# Main_Board_Module.net
KiCad netlist of a schematic drawn in EAGLE
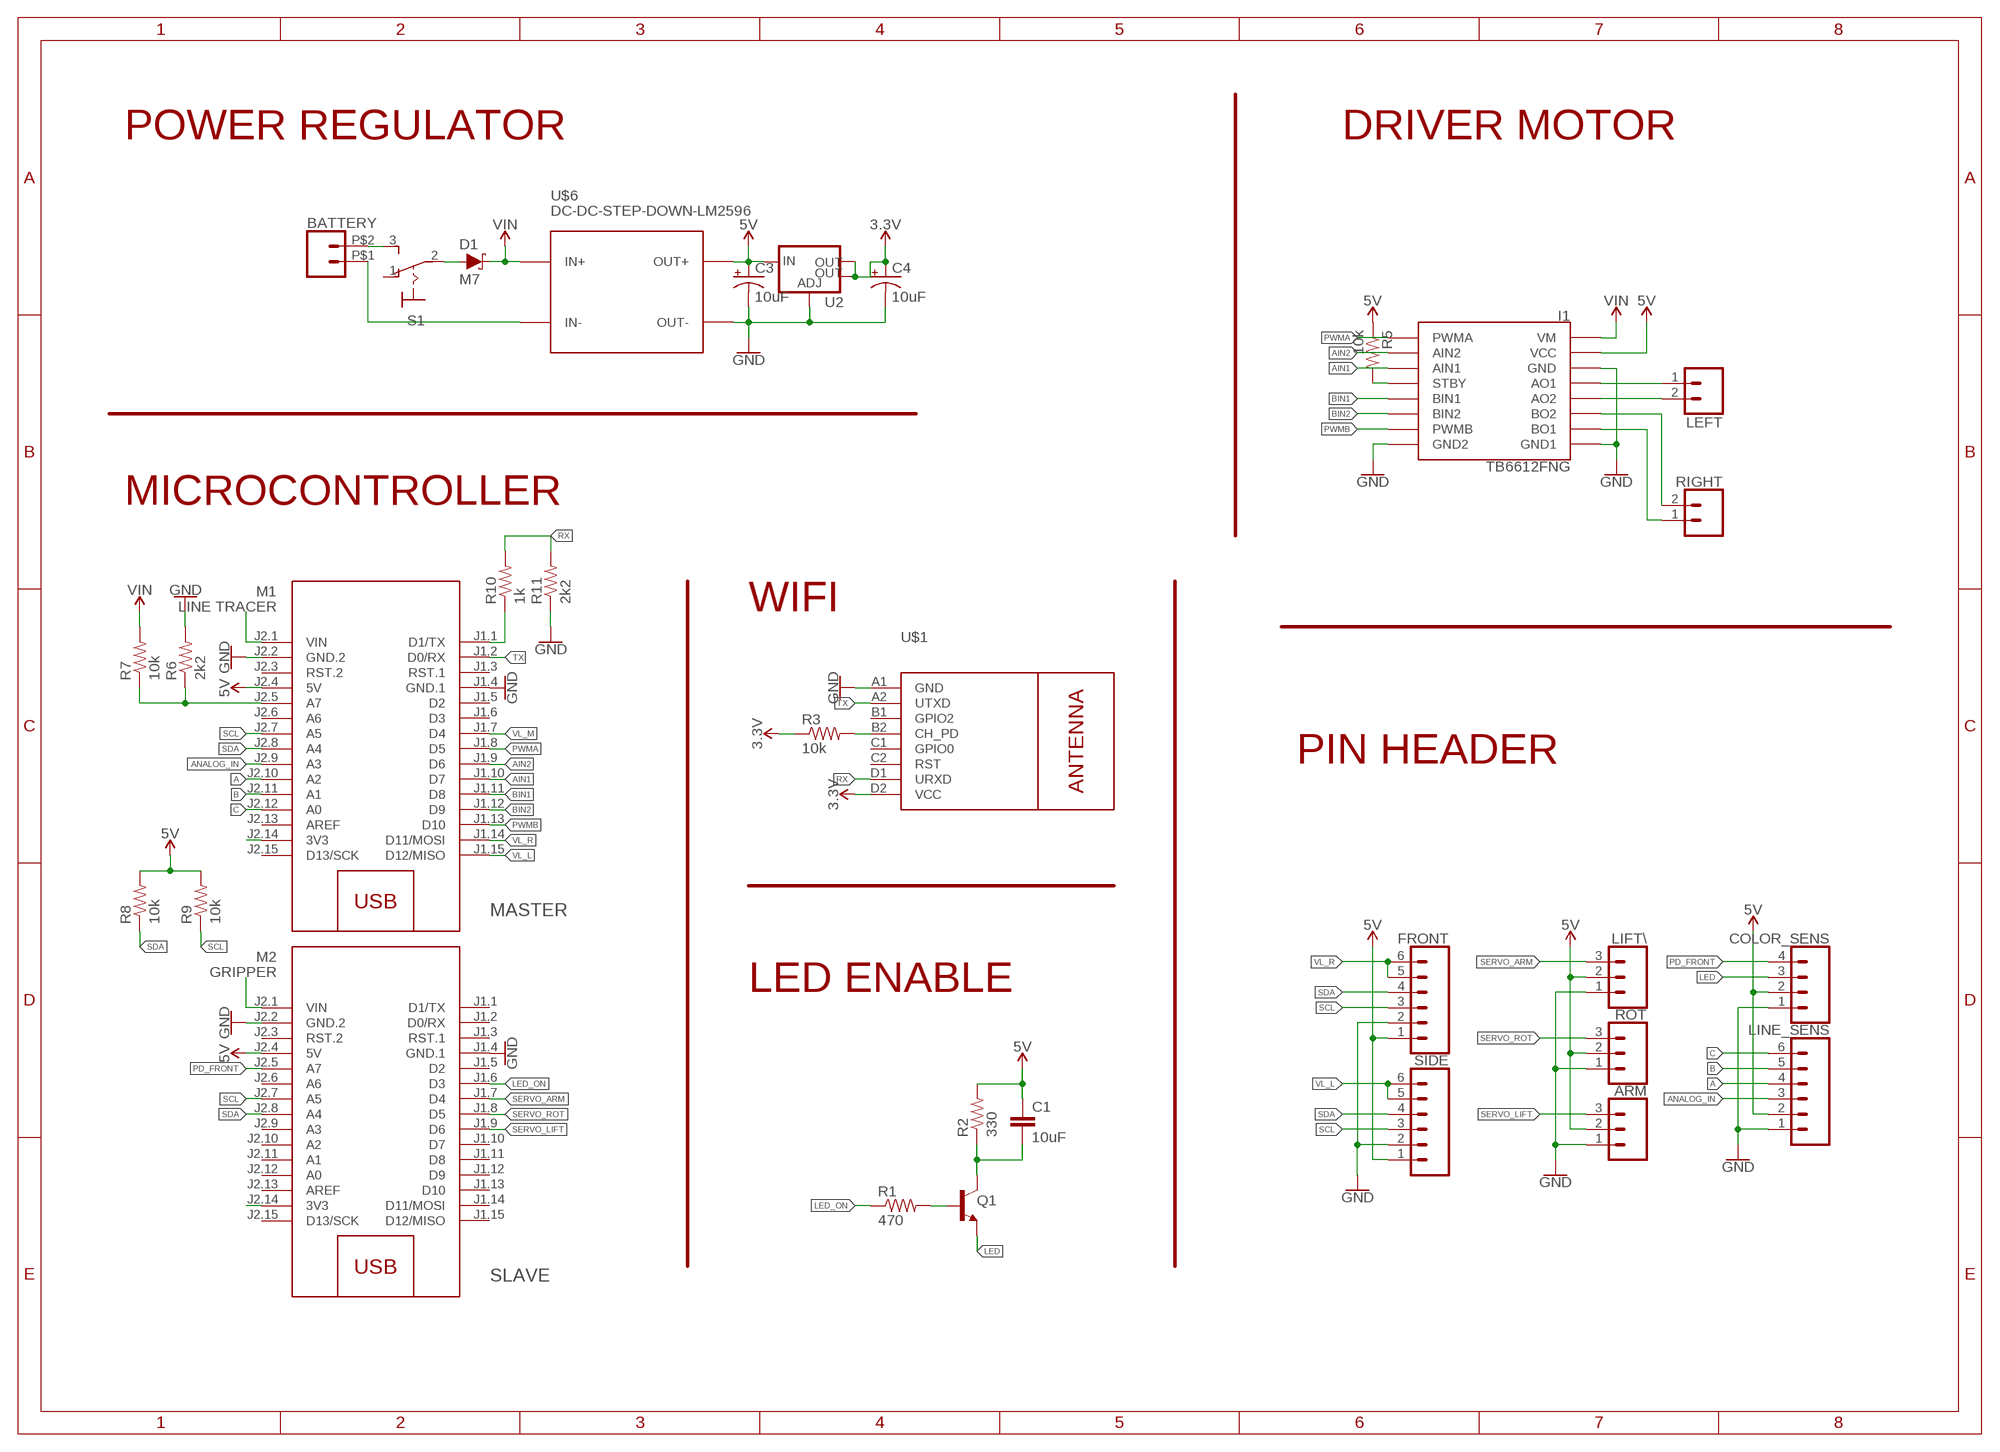
[diagram p0: schematic, sheet 1]

(export (version "E")
  (design (tool "Eeschema 10.0.6"))
  (components
    (comp (ref "ARM")
      (value "CONN_03")
      (footprint "eagle-import:1X03")
      (libsource (lib "eagle-import") (part "CONN_03"))
    )
    (comp (ref "BATTERY")
      (value "CONN_02PTH2")
      (footprint "eagle-import:1X02_BIG")
      (libsource (lib "eagle-import") (part "CONN_02PTH2"))
    )
    (comp (ref "C1")
      (value "10uF")
      (footprint "eagle-import:C1206")
      (libsource (lib "eagle-import") (part "C-EUC1206"))
    )
    (comp (ref "C3")
      (value "10uF")
      (footprint "eagle-import:EIA3216")
      (libsource (lib "eagle-import") (part "10UF-POLAR-EIA3216-16V-10%(TANT)"))
    )
    (comp (ref "C4")
      (value "10uF")
      (footprint "eagle-import:EIA3216")
      (libsource (lib "eagle-import") (part "10UF-POLAR-EIA3216-16V-10%(TANT)"))
    )
    (comp (ref "COLOR_SENS")
      (value "CONN_04")
      (footprint "eagle-import:1X04")
      (libsource (lib "eagle-import") (part "CONN_04"))
    )
    (comp (ref "D1")
      (value "M7")
      (footprint "eagle-import:SMA-DIODE")
      (libsource (lib "eagle-import") (part "DIODE-SCHOTTKY-SS14"))
    )
    (comp (ref "FRONT")
      (value "CONN_06SILK_FEMALE_PTH")
      (footprint "eagle-import:1X06")
      (libsource (lib "eagle-import") (part "CONN_06SILK_FEMALE_PTH"))
    )
    (comp (ref "I1")
      (value "TB6612FNG_MODULE")
      (footprint "eagle-import:TB6612FNG")
      (libsource (lib "eagle-import") (part "TB6612FNG_MODULE"))
    )
    (comp (ref "LEFT")
      (value "CONN_02POLAR")
      (footprint "eagle-import:MOLEX-1X2")
      (libsource (lib "eagle-import") (part "CONN_02POLAR"))
    )
    (comp (ref "LIFT\\")
      (value "CONN_03")
      (footprint "eagle-import:1X03")
      (libsource (lib "eagle-import") (part "CONN_03"))
    )
    (comp (ref "LINE_SENS")
      (value "CONN_06SILK_FEMALE_PTH")
      (footprint "eagle-import:1X06")
      (libsource (lib "eagle-import") (part "CONN_06SILK_FEMALE_PTH"))
    )
    (comp (ref "M1")
      (value "LINE TRACER")
      (footprint "eagle-import:ARDUINO-NANO-3.0")
      (libsource (lib "eagle-import") (part "ARDUINO-NANO-3.0"))
    )
    (comp (ref "M2")
      (value "GRIPPER")
      (footprint "eagle-import:ARDUINO-NANO-3.0")
      (libsource (lib "eagle-import") (part "ARDUINO-NANO-3.0"))
    )
    (comp (ref "Q1")
      (value "TRANS_NPN-MMBT2222AL")
      (footprint "eagle-import:SOT23-3")
      (libsource (lib "eagle-import") (part "TRANS_NPN-MMBT2222AL"))
    )
    (comp (ref "R1")
      (value "470")
      (footprint "eagle-import:R1206")
      (libsource (lib "eagle-import") (part "rcl_334_R-US_R1206"))
    )
    (comp (ref "R2")
      (value "330")
      (footprint "eagle-import:R1206")
      (libsource (lib "eagle-import") (part "rcl_334_R-US_R1206"))
    )
    (comp (ref "R3")
      (value "10k")
      (footprint "eagle-import:R1206")
      (libsource (lib "eagle-import") (part "rcl_334_R-US_R1206"))
    )
    (comp (ref "R5")
      (value "10k")
      (footprint "eagle-import:0207_9")
      (libsource (lib "eagle-import") (part "R-US_0207/9"))
    )
    (comp (ref "R6")
      (value "2k2")
      (footprint "eagle-import:0207_9")
      (libsource (lib "eagle-import") (part "R-US_0207/9"))
    )
    (comp (ref "R7")
      (value "10k")
      (footprint "eagle-import:0207_9")
      (libsource (lib "eagle-import") (part "R-US_0207/9"))
    )
    (comp (ref "R8")
      (value "10k")
      (footprint "eagle-import:0207_9")
      (libsource (lib "eagle-import") (part "R-US_0207/9"))
    )
    (comp (ref "R9")
      (value "10k")
      (footprint "eagle-import:0207_9")
      (libsource (lib "eagle-import") (part "R-US_0207/9"))
    )
    (comp (ref "R10")
      (value "1k")
      (footprint "eagle-import:0207_9")
      (libsource (lib "eagle-import") (part "R-US_0207/9"))
    )
    (comp (ref "R11")
      (value "2k2")
      (footprint "eagle-import:0207_9")
      (libsource (lib "eagle-import") (part "R-US_0207/9"))
    )
    (comp (ref "RIGHT")
      (value "CONN_02POLAR")
      (footprint "eagle-import:MOLEX-1X2")
      (libsource (lib "eagle-import") (part "CONN_02POLAR"))
    )
    (comp (ref "ROT")
      (value "CONN_03")
      (footprint "eagle-import:1X03")
      (libsource (lib "eagle-import") (part "CONN_03"))
    )
    (comp (ref "S1")
      (value "320-916")
      (footprint "eagle-import:320-916")
      (libsource (lib "eagle-import") (part "320-916"))
    )
    (comp (ref "SIDE")
      (value "CONN_06SILK_FEMALE_PTH")
      (footprint "eagle-import:1X06")
      (libsource (lib "eagle-import") (part "CONN_06SILK_FEMALE_PTH"))
    )
    (comp (ref "U$1")
      (value "WIRELESS-WIFI-ESP-01")
      (footprint "eagle-import:WIRELESS-WIFI-ESP-01")
      (libsource (lib "eagle-import") (part "WIRELESS-WIFI-ESP-01"))
    )
    (comp (ref "U$6")
      (value "DC-DC-STEP-DOWN-LM2596")
      (footprint "eagle-import:DC-DC-STEP-DOWN-LM2596")
      (libsource (lib "eagle-import") (part "DC-DC-STEP-DOWN-LM2596"))
    )
    (comp (ref "U2")
      (value "V_REG_LM1117SOT223")
      (footprint "eagle-import:SOT223")
      (libsource (lib "eagle-import") (part "V_REG_LM1117SOT223"))
    )
  )
  (nets
    (net (code "1") (name "3.3V") (class "Default")
      (node (ref "C4") (pin "+") (pinfunction "+_+") (pintype "passive"))
      (node (ref "R3") (pin "1") (pinfunction "1_1") (pintype "passive"))
      (node (ref "U$1") (pin "D2") (pinfunction "VCC_D2") (pintype "power_in"))
      (node (ref "U2") (pin "2") (pinfunction "OUT_2") (pintype "output"))
      (node (ref "U2") (pin "4") (pinfunction "OUT_4") (pintype "output"))
    )
    (net (code "2") (name "5V") (class "Default")
      (node (ref "ARM") (pin "2") (pinfunction "2_2") (pintype "passive"))
      (node (ref "C1") (pin "1") (pinfunction "1_1") (pintype "passive"))
      (node (ref "C3") (pin "+") (pinfunction "+_+") (pintype "passive"))
      (node (ref "COLOR_SENS") (pin "2") (pinfunction "2_2") (pintype "passive"))
      (node (ref "FRONT") (pin "1") (pinfunction "1_1") (pintype "passive"))
      (node (ref "I1") (pin "VCC") (pinfunction "VCC_VCC") (pintype "power_in"))
      (node (ref "LIFT\\") (pin "2") (pinfunction "2_2") (pintype "passive"))
      (node (ref "LINE_SENS") (pin "2") (pinfunction "2_2") (pintype "passive"))
      (node (ref "M1") (pin "J2.4") (pinfunction "5V_J2.4") (pintype "power_in"))
      (node (ref "M2") (pin "J2.4") (pinfunction "5V_J2.4") (pintype "power_in"))
      (node (ref "R2") (pin "2") (pinfunction "2_2") (pintype "passive"))
      (node (ref "R5") (pin "1") (pinfunction "1_1") (pintype "passive"))
      (node (ref "R8") (pin "2") (pinfunction "2_2") (pintype "passive"))
      (node (ref "R9") (pin "2") (pinfunction "2_2") (pintype "passive"))
      (node (ref "ROT") (pin "2") (pinfunction "2_2") (pintype "passive"))
      (node (ref "SIDE") (pin "1") (pinfunction "1_1") (pintype "passive"))
      (node (ref "U$6") (pin "OUT+") (pinfunction "OUT+_OUT+") (pintype "bidirectional"))
      (node (ref "U2") (pin "3") (pinfunction "IN_3") (pintype "input"))
    )
    (net (code "3") (name "A") (class "Default")
      (node (ref "LINE_SENS") (pin "4") (pinfunction "4_4") (pintype "passive"))
      (node (ref "M1") (pin "J2.10") (pinfunction "A2_J2.10") (pintype "bidirectional"))
    )
    (net (code "4") (name "AIN1") (class "Default")
      (node (ref "I1") (pin "AIN1") (pinfunction "AIN1_AIN1") (pintype "input"))
      (node (ref "M1") (pin "J1.10") (pinfunction "D7_J1.10") (pintype "bidirectional"))
    )
    (net (code "5") (name "AIN2") (class "Default")
      (node (ref "I1") (pin "AIN2") (pinfunction "AIN2_AIN2") (pintype "input"))
      (node (ref "M1") (pin "J1.9") (pinfunction "D6_J1.9") (pintype "bidirectional"))
    )
    (net (code "6") (name "ANALOG_IN") (class "Default")
      (node (ref "LINE_SENS") (pin "3") (pinfunction "3_3") (pintype "passive"))
      (node (ref "M1") (pin "J2.9") (pinfunction "A3_J2.9") (pintype "bidirectional"))
    )
    (net (code "7") (name "B") (class "Default")
      (node (ref "LINE_SENS") (pin "5") (pinfunction "5_5") (pintype "passive"))
      (node (ref "M1") (pin "J2.11") (pinfunction "A1_J2.11") (pintype "bidirectional"))
    )
    (net (code "8") (name "BIN1") (class "Default")
      (node (ref "I1") (pin "BIN1") (pinfunction "BIN1_BIN1") (pintype "input"))
      (node (ref "M1") (pin "J1.11") (pinfunction "D8_J1.11") (pintype "bidirectional"))
    )
    (net (code "9") (name "BIN2") (class "Default")
      (node (ref "I1") (pin "BIN2") (pinfunction "BIN2_BIN2") (pintype "input"))
      (node (ref "M1") (pin "J1.12") (pinfunction "D9_J1.12") (pintype "bidirectional"))
    )
    (net (code "10") (name "C") (class "Default")
      (node (ref "LINE_SENS") (pin "6") (pinfunction "6_6") (pintype "passive"))
      (node (ref "M1") (pin "J2.12") (pinfunction "A0_J2.12") (pintype "bidirectional"))
    )
    (net (code "11") (name "GND") (class "Default")
      (node (ref "ARM") (pin "1") (pinfunction "1_1") (pintype "passive"))
      (node (ref "C3") (pin "-") (pinfunction "-_-") (pintype "passive"))
      (node (ref "C4") (pin "-") (pinfunction "-_-") (pintype "passive"))
      (node (ref "COLOR_SENS") (pin "1") (pinfunction "1_1") (pintype "passive"))
      (node (ref "FRONT") (pin "2") (pinfunction "2_2") (pintype "passive"))
      (node (ref "I1") (pin "GND") (pinfunction "GND_GND") (pintype "power_in"))
      (node (ref "I1") (pin "GND1") (pinfunction "GND1_GND1") (pintype "power_in"))
      (node (ref "I1") (pin "GND2") (pinfunction "GND2_GND2") (pintype "power_in"))
      (node (ref "LIFT\\") (pin "1") (pinfunction "1_1") (pintype "passive"))
      (node (ref "LINE_SENS") (pin "1") (pinfunction "1_1") (pintype "passive"))
      (node (ref "M1") (pin "J1.4") (pinfunction "GND.1_J1.4") (pintype "power_in"))
      (node (ref "M1") (pin "J2.2") (pinfunction "GND.2_J2.2") (pintype "power_in"))
      (node (ref "M2") (pin "J1.4") (pinfunction "GND.1_J1.4") (pintype "power_in"))
      (node (ref "M2") (pin "J2.2") (pinfunction "GND.2_J2.2") (pintype "power_in"))
      (node (ref "R11") (pin "1") (pinfunction "1_1") (pintype "passive"))
      (node (ref "R6") (pin "2") (pinfunction "2_2") (pintype "passive"))
      (node (ref "ROT") (pin "1") (pinfunction "1_1") (pintype "passive"))
      (node (ref "SIDE") (pin "2") (pinfunction "2_2") (pintype "passive"))
      (node (ref "U$1") (pin "A1") (pinfunction "GND_A1") (pintype "power_in"))
      (node (ref "U$6") (pin "OUT-") (pinfunction "OUT-_OUT-") (pintype "bidirectional"))
      (node (ref "U2") (pin "1") (pinfunction "ADJ_1") (pintype "input"))
    )
    (net (code "12") (name "LED") (class "Default")
      (node (ref "COLOR_SENS") (pin "3") (pinfunction "3_3") (pintype "passive"))
      (node (ref "Q1") (pin "2") (pinfunction "E_2") (pintype "passive"))
    )
    (net (code "13") (name "LED_ON") (class "Default")
      (node (ref "M2") (pin "J1.6") (pinfunction "D3_J1.6") (pintype "bidirectional"))
      (node (ref "R1") (pin "1") (pinfunction "1_1") (pintype "passive"))
    )
    (net (code "14") (name "Net-(BATTERY-1)") (class "Default")
      (node (ref "BATTERY") (pin "P$1") (pinfunction "1_P$1") (pintype "passive"))
      (node (ref "U$6") (pin "IN-") (pinfunction "IN-_IN-") (pintype "bidirectional"))
    )
    (net (code "15") (name "Net-(BATTERY-2)") (class "Default")
      (node (ref "BATTERY") (pin "P$2") (pinfunction "2_P$2") (pintype "passive"))
      (node (ref "S1") (pin "3") (pinfunction "S_3") (pintype "passive"))
    )
    (net (code "16") (name "Net-(I1-PadAO1)") (class "Default")
      (node (ref "I1") (pin "AO1") (pinfunction "AO1_AO1") (pintype "output"))
      (node (ref "LEFT") (pin "1") (pinfunction "1_1") (pintype "passive"))
    )
    (net (code "17") (name "Net-(I1-PadAO2)") (class "Default")
      (node (ref "I1") (pin "AO2") (pinfunction "AO2_AO2") (pintype "output"))
      (node (ref "LEFT") (pin "2") (pinfunction "2_2") (pintype "passive"))
    )
    (net (code "18") (name "Net-(I1-PadBO1)") (class "Default")
      (node (ref "I1") (pin "BO1") (pinfunction "BO1_BO1") (pintype "output"))
      (node (ref "RIGHT") (pin "1") (pinfunction "1_1") (pintype "passive"))
    )
    (net (code "19") (name "Net-(I1-PadBO2)") (class "Default")
      (node (ref "I1") (pin "BO2") (pinfunction "BO2_BO2") (pintype "output"))
      (node (ref "RIGHT") (pin "2") (pinfunction "2_2") (pintype "passive"))
    )
    (net (code "20") (name "Net-(I1-PadSTBY)") (class "Default")
      (node (ref "I1") (pin "STBY") (pinfunction "STBY_STBY") (pintype "bidirectional"))
      (node (ref "R5") (pin "2") (pinfunction "2_2") (pintype "passive"))
    )
    (net (code "21") (name "Net-(M1-A7)") (class "Default")
      (node (ref "M1") (pin "J2.5") (pinfunction "A7_J2.5") (pintype "bidirectional"))
      (node (ref "R6") (pin "1") (pinfunction "1_1") (pintype "passive"))
      (node (ref "R7") (pin "1") (pinfunction "1_1") (pintype "passive"))
    )
    (net (code "22") (name "Net-(M1-D1{slash}TX)") (class "Default")
      (node (ref "M1") (pin "J1.1") (pinfunction "D1/TX_J1.1") (pintype "bidirectional"))
      (node (ref "R10") (pin "1") (pinfunction "1_1") (pintype "passive"))
    )
    (net (code "23") (name "Net-(Q1-B)") (class "Default")
      (node (ref "Q1") (pin "1") (pinfunction "B_1") (pintype "passive"))
      (node (ref "R1") (pin "2") (pinfunction "2_2") (pintype "passive"))
    )
    (net (code "24") (name "Net-(Q1-C)") (class "Default")
      (node (ref "C1") (pin "2") (pinfunction "2_2") (pintype "passive"))
      (node (ref "Q1") (pin "3") (pinfunction "C_3") (pintype "passive"))
      (node (ref "R2") (pin "1") (pinfunction "1_1") (pintype "passive"))
    )
    (net (code "25") (name "Net-(S1-P)") (class "Default")
      (node (ref "D1") (pin "A") (pinfunction "A_A") (pintype "passive"))
      (node (ref "S1") (pin "2") (pinfunction "P_2") (pintype "passive"))
    )
    (net (code "26") (name "Net-(U$1-CH_PD)") (class "Default")
      (node (ref "R3") (pin "2") (pinfunction "2_2") (pintype "passive"))
      (node (ref "U$1") (pin "B2") (pinfunction "CH_PD_B2") (pintype "bidirectional"))
    )
    (net (code "27") (name "PD_FRONT") (class "Default")
      (node (ref "COLOR_SENS") (pin "4") (pinfunction "4_4") (pintype "passive"))
      (node (ref "M2") (pin "J2.5") (pinfunction "A7_J2.5") (pintype "bidirectional"))
    )
    (net (code "28") (name "PWMA") (class "Default")
      (node (ref "I1") (pin "PWMA") (pinfunction "PWMA_PWMA") (pintype "input"))
      (node (ref "M1") (pin "J1.8") (pinfunction "D5_J1.8") (pintype "bidirectional"))
    )
    (net (code "29") (name "PWMB") (class "Default")
      (node (ref "I1") (pin "PWMB") (pinfunction "PWMB_PWMB") (pintype "input"))
      (node (ref "M1") (pin "J1.13") (pinfunction "D10_J1.13") (pintype "bidirectional"))
    )
    (net (code "30") (name "RX") (class "Default")
      (node (ref "R10") (pin "2") (pinfunction "2_2") (pintype "passive"))
      (node (ref "R11") (pin "2") (pinfunction "2_2") (pintype "passive"))
      (node (ref "U$1") (pin "D1") (pinfunction "URXD_D1") (pintype "bidirectional"))
    )
    (net (code "31") (name "SCL") (class "Default")
      (node (ref "FRONT") (pin "3") (pinfunction "3_3") (pintype "passive"))
      (node (ref "M1") (pin "J2.7") (pinfunction "A5_J2.7") (pintype "bidirectional"))
      (node (ref "M2") (pin "J2.7") (pinfunction "A5_J2.7") (pintype "bidirectional"))
      (node (ref "R9") (pin "1") (pinfunction "1_1") (pintype "passive"))
      (node (ref "SIDE") (pin "3") (pinfunction "3_3") (pintype "passive"))
    )
    (net (code "32") (name "SDA") (class "Default")
      (node (ref "FRONT") (pin "4") (pinfunction "4_4") (pintype "passive"))
      (node (ref "M1") (pin "J2.8") (pinfunction "A4_J2.8") (pintype "bidirectional"))
      (node (ref "M2") (pin "J2.8") (pinfunction "A4_J2.8") (pintype "bidirectional"))
      (node (ref "R8") (pin "1") (pinfunction "1_1") (pintype "passive"))
      (node (ref "SIDE") (pin "4") (pinfunction "4_4") (pintype "passive"))
    )
    (net (code "33") (name "SERVO_ARM") (class "Default")
      (node (ref "LIFT\\") (pin "3") (pinfunction "3_3") (pintype "passive"))
      (node (ref "M2") (pin "J1.7") (pinfunction "D4_J1.7") (pintype "bidirectional"))
    )
    (net (code "34") (name "SERVO_LIFT") (class "Default")
      (node (ref "ARM") (pin "3") (pinfunction "3_3") (pintype "passive"))
      (node (ref "M2") (pin "J1.9") (pinfunction "D6_J1.9") (pintype "bidirectional"))
    )
    (net (code "35") (name "SERVO_ROT") (class "Default")
      (node (ref "M2") (pin "J1.8") (pinfunction "D5_J1.8") (pintype "bidirectional"))
      (node (ref "ROT") (pin "3") (pinfunction "3_3") (pintype "passive"))
    )
    (net (code "36") (name "TX") (class "Default")
      (node (ref "M1") (pin "J1.2") (pinfunction "D0/RX_J1.2") (pintype "bidirectional"))
      (node (ref "U$1") (pin "A2") (pinfunction "UTXD_A2") (pintype "bidirectional"))
    )
    (net (code "37") (name "VIN") (class "Default")
      (node (ref "D1") (pin "C") (pinfunction "C_C") (pintype "passive"))
      (node (ref "I1") (pin "VM") (pinfunction "VM_VM") (pintype "power_in"))
      (node (ref "R7") (pin "2") (pinfunction "2_2") (pintype "passive"))
      (node (ref "U$6") (pin "IN+") (pinfunction "IN+_IN+") (pintype "bidirectional"))
    )
    (net (code "38") (name "VL_L") (class "Default")
      (node (ref "M1") (pin "J1.15") (pinfunction "D12/MISO_J1.15") (pintype "bidirectional"))
      (node (ref "SIDE") (pin "5") (pinfunction "5_5") (pintype "passive"))
      (node (ref "SIDE") (pin "6") (pinfunction "6_6") (pintype "passive"))
    )
    (net (code "39") (name "VL_M") (class "Default")
      (node (ref "M1") (pin "J1.7") (pinfunction "D4_J1.7") (pintype "bidirectional"))
    )
    (net (code "40") (name "VL_R") (class "Default")
      (node (ref "FRONT") (pin "5") (pinfunction "5_5") (pintype "passive"))
      (node (ref "FRONT") (pin "6") (pinfunction "6_6") (pintype "passive"))
      (node (ref "M1") (pin "J1.14") (pinfunction "D11/MOSI_J1.14") (pintype "bidirectional"))
    )
    (net (code "41") (name "unconnected-(M1-3V3-PadJ2.14)") (class "Default")
      (node (ref "M1") (pin "J2.14") (pinfunction "3V3_J2.14") (pintype "power_in"))
    )
    (net (code "42") (name "unconnected-(M1-A6-PadJ2.6)") (class "Default")
      (node (ref "M1") (pin "J2.6") (pinfunction "A6_J2.6") (pintype "bidirectional"))
    )
    (net (code "43") (name "unconnected-(M1-AREF-PadJ2.13)") (class "Default")
      (node (ref "M1") (pin "J2.13") (pinfunction "AREF_J2.13") (pintype "bidirectional"))
    )
    (net (code "44") (name "unconnected-(M1-D2-PadJ1.5)") (class "Default")
      (node (ref "M1") (pin "J1.5") (pinfunction "D2_J1.5") (pintype "bidirectional"))
    )
    (net (code "45") (name "unconnected-(M1-D3-PadJ1.6)") (class "Default")
      (node (ref "M1") (pin "J1.6") (pinfunction "D3_J1.6") (pintype "bidirectional"))
    )
    (net (code "46") (name "unconnected-(M1-D13{slash}SCK-PadJ2.15)") (class "Default")
      (node (ref "M1") (pin "J2.15") (pinfunction "D13/SCK_J2.15") (pintype "bidirectional"))
    )
    (net (code "47") (name "unconnected-(M1-RST.1-PadJ1.3)") (class "Default")
      (node (ref "M1") (pin "J1.3") (pinfunction "RST.1_J1.3") (pintype "bidirectional"))
    )
    (net (code "48") (name "unconnected-(M1-RST.2-PadJ2.3)") (class "Default")
      (node (ref "M1") (pin "J2.3") (pinfunction "RST.2_J2.3") (pintype "bidirectional"))
    )
    (net (code "49") (name "unconnected-(M1-VIN-PadJ2.1)") (class "Default")
      (node (ref "M1") (pin "J2.1") (pinfunction "VIN_J2.1") (pintype "power_in"))
    )
    (net (code "50") (name "unconnected-(M2-3V3-PadJ2.14)") (class "Default")
      (node (ref "M2") (pin "J2.14") (pinfunction "3V3_J2.14") (pintype "power_in"))
    )
    (net (code "51") (name "unconnected-(M2-A0-PadJ2.12)") (class "Default")
      (node (ref "M2") (pin "J2.12") (pinfunction "A0_J2.12") (pintype "bidirectional"))
    )
    (net (code "52") (name "unconnected-(M2-A1-PadJ2.11)") (class "Default")
      (node (ref "M2") (pin "J2.11") (pinfunction "A1_J2.11") (pintype "bidirectional"))
    )
    (net (code "53") (name "unconnected-(M2-A2-PadJ2.10)") (class "Default")
      (node (ref "M2") (pin "J2.10") (pinfunction "A2_J2.10") (pintype "bidirectional"))
    )
    (net (code "54") (name "unconnected-(M2-A3-PadJ2.9)") (class "Default")
      (node (ref "M2") (pin "J2.9") (pinfunction "A3_J2.9") (pintype "bidirectional"))
    )
    (net (code "55") (name "unconnected-(M2-A6-PadJ2.6)") (class "Default")
      (node (ref "M2") (pin "J2.6") (pinfunction "A6_J2.6") (pintype "bidirectional"))
    )
    (net (code "56") (name "unconnected-(M2-AREF-PadJ2.13)") (class "Default")
      (node (ref "M2") (pin "J2.13") (pinfunction "AREF_J2.13") (pintype "bidirectional"))
    )
    (net (code "57") (name "unconnected-(M2-D0{slash}RX-PadJ1.2)") (class "Default")
      (node (ref "M2") (pin "J1.2") (pinfunction "D0/RX_J1.2") (pintype "bidirectional"))
    )
    (net (code "58") (name "unconnected-(M2-D1{slash}TX-PadJ1.1)") (class "Default")
      (node (ref "M2") (pin "J1.1") (pinfunction "D1/TX_J1.1") (pintype "bidirectional"))
    )
    (net (code "59") (name "unconnected-(M2-D2-PadJ1.5)") (class "Default")
      (node (ref "M2") (pin "J1.5") (pinfunction "D2_J1.5") (pintype "bidirectional"))
    )
    (net (code "60") (name "unconnected-(M2-D7-PadJ1.10)") (class "Default")
      (node (ref "M2") (pin "J1.10") (pinfunction "D7_J1.10") (pintype "bidirectional"))
    )
    (net (code "61") (name "unconnected-(M2-D8-PadJ1.11)") (class "Default")
      (node (ref "M2") (pin "J1.11") (pinfunction "D8_J1.11") (pintype "bidirectional"))
    )
    (net (code "62") (name "unconnected-(M2-D9-PadJ1.12)") (class "Default")
      (node (ref "M2") (pin "J1.12") (pinfunction "D9_J1.12") (pintype "bidirectional"))
    )
    (net (code "63") (name "unconnected-(M2-D10-PadJ1.13)") (class "Default")
      (node (ref "M2") (pin "J1.13") (pinfunction "D10_J1.13") (pintype "bidirectional"))
    )
    (net (code "64") (name "unconnected-(M2-D11{slash}MOSI-PadJ1.14)") (class "Default")
      (node (ref "M2") (pin "J1.14") (pinfunction "D11/MOSI_J1.14") (pintype "bidirectional"))
    )
    (net (code "65") (name "unconnected-(M2-D12{slash}MISO-PadJ1.15)") (class "Default")
      (node (ref "M2") (pin "J1.15") (pinfunction "D12/MISO_J1.15") (pintype "bidirectional"))
    )
    (net (code "66") (name "unconnected-(M2-D13{slash}SCK-PadJ2.15)") (class "Default")
      (node (ref "M2") (pin "J2.15") (pinfunction "D13/SCK_J2.15") (pintype "bidirectional"))
    )
    (net (code "67") (name "unconnected-(M2-RST.1-PadJ1.3)") (class "Default")
      (node (ref "M2") (pin "J1.3") (pinfunction "RST.1_J1.3") (pintype "bidirectional"))
    )
    (net (code "68") (name "unconnected-(M2-RST.2-PadJ2.3)") (class "Default")
      (node (ref "M2") (pin "J2.3") (pinfunction "RST.2_J2.3") (pintype "bidirectional"))
    )
    (net (code "69") (name "unconnected-(M2-VIN-PadJ2.1)") (class "Default")
      (node (ref "M2") (pin "J2.1") (pinfunction "VIN_J2.1") (pintype "power_in"))
    )
    (net (code "70") (name "unconnected-(S1-O-Pad1)") (class "Default")
      (node (ref "S1") (pin "1") (pinfunction "O_1") (pintype "passive"))
    )
    (net (code "71") (name "unconnected-(U$1-GPIO0-PadC1)") (class "Default")
      (node (ref "U$1") (pin "C1") (pinfunction "GPIO0_C1") (pintype "bidirectional"))
    )
    (net (code "72") (name "unconnected-(U$1-GPIO2-PadB1)") (class "Default")
      (node (ref "U$1") (pin "B1") (pinfunction "GPIO2_B1") (pintype "bidirectional"))
    )
    (net (code "73") (name "unconnected-(U$1-RST-PadC2)") (class "Default")
      (node (ref "U$1") (pin "C2") (pinfunction "RST_C2") (pintype "bidirectional"))
    )
  )
)
